# opo_iki.net
KiCad netlist of a schematic drawn in EAGLE
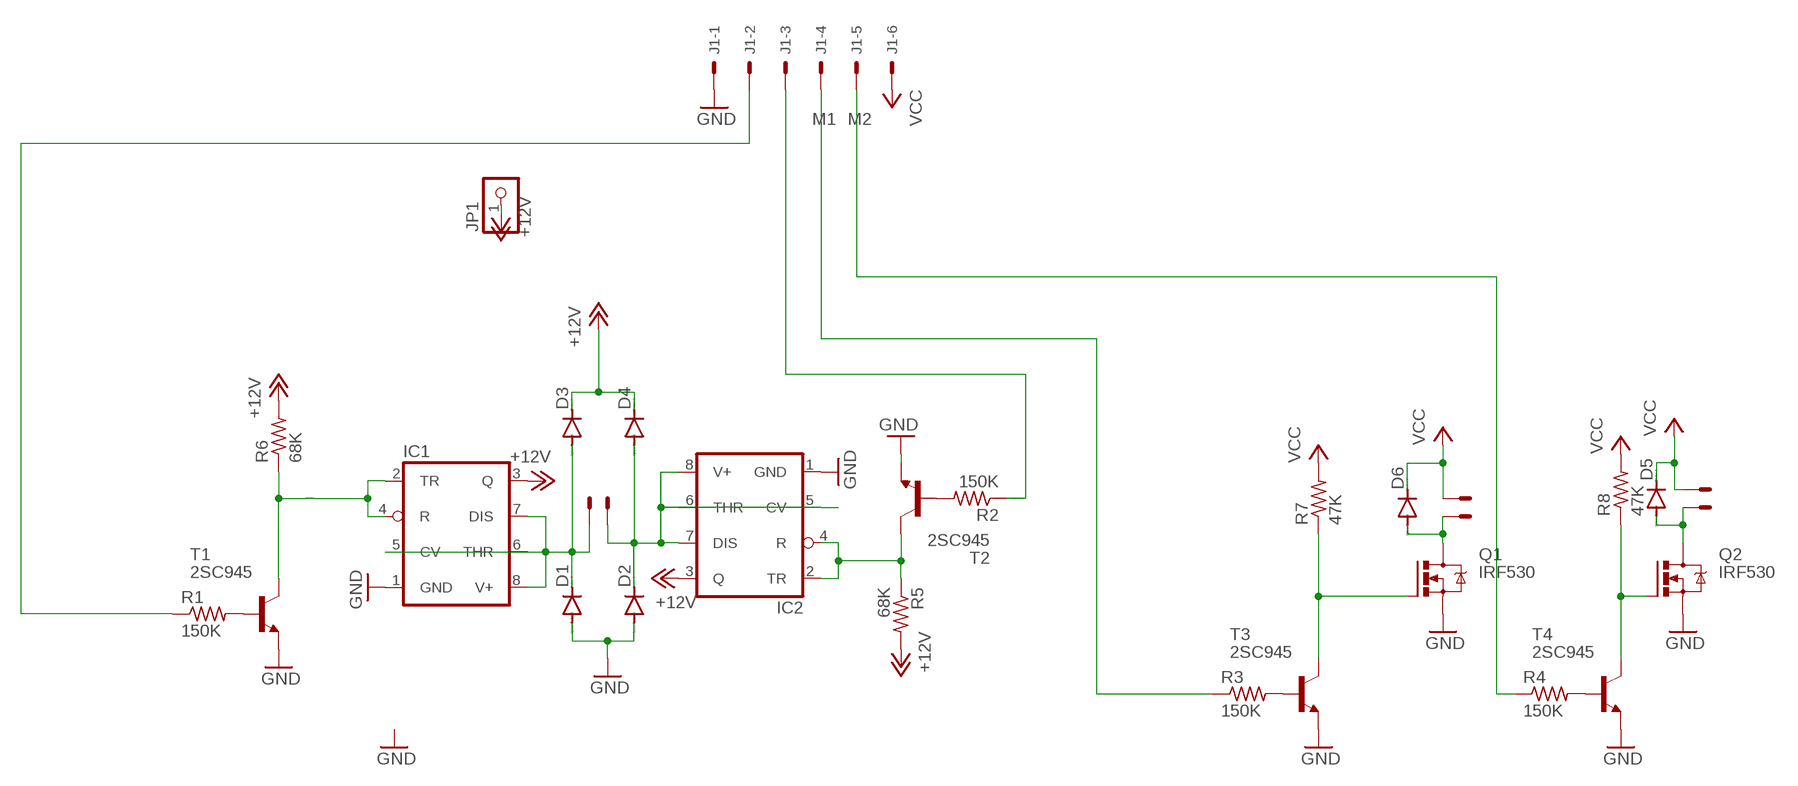
[diagram p0: schematic, sheet 1]

(export (version "E")
  (design (tool "Eeschema 10.0.6"))
  (components
    (comp (ref "D1")
      (value "1N4004")
      (footprint "eagle-import:DO41-10")
      (libsource (lib "eagle-import") (part "1N4004"))
    )
    (comp (ref "D2")
      (value "1N4004")
      (footprint "eagle-import:DO41-10")
      (libsource (lib "eagle-import") (part "1N4004"))
    )
    (comp (ref "D3")
      (value "1N4004")
      (footprint "eagle-import:DO41-10")
      (libsource (lib "eagle-import") (part "1N4004"))
    )
    (comp (ref "D4")
      (value "1N4004")
      (footprint "eagle-import:DO41-10")
      (libsource (lib "eagle-import") (part "1N4004"))
    )
    (comp (ref "D5")
      (value "1N4004")
      (footprint "eagle-import:DO41-10")
      (libsource (lib "eagle-import") (part "1N4004"))
    )
    (comp (ref "D6")
      (value "1N4004")
      (footprint "eagle-import:DO41-10")
      (libsource (lib "eagle-import") (part "1N4004"))
    )
    (comp (ref "IC1")
      (value "LM555D")
      (footprint "eagle-import:SO08")
      (libsource (lib "eagle-import") (part "555DLM"))
    )
    (comp (ref "IC2")
      (value "LM555D")
      (footprint "eagle-import:SO08")
      (libsource (lib "eagle-import") (part "555DLM"))
    )
    (comp (ref "J1")
      (value "22-27-2061-06")
      (footprint "eagle-import:6410-06")
      (fields (field (name "MF") "MOLEX"))
      (libsource (lib "eagle-import") (part "22-?-0627-2061"))
    )
    (comp (ref "JP1")
      (value "PINHD-1X1")
      (footprint "eagle-import:1X01")
      (libsource (lib "eagle-import") (part "PINHD-1X1"))
    )
    (comp (ref "Q1")
      (value "IRF530")
      (footprint "eagle-import:TO220BV")
      (libsource (lib "eagle-import") (part "IRF530"))
    )
    (comp (ref "Q2")
      (value "IRF530")
      (footprint "eagle-import:TO220BV")
      (libsource (lib "eagle-import") (part "IRF530"))
    )
    (comp (ref "R1")
      (value "150K")
      (footprint "eagle-import:0309_10")
      (libsource (lib "eagle-import") (part "R-US_0309/10"))
    )
    (comp (ref "R2")
      (value "150K")
      (footprint "eagle-import:0309_10")
      (libsource (lib "eagle-import") (part "R-US_0309/10"))
    )
    (comp (ref "R3")
      (value "150K")
      (footprint "eagle-import:0309_10")
      (libsource (lib "eagle-import") (part "R-US_0309/10"))
    )
    (comp (ref "R4")
      (value "150K")
      (footprint "eagle-import:0309_10")
      (libsource (lib "eagle-import") (part "R-US_0309/10"))
    )
    (comp (ref "R5")
      (value "68K")
      (footprint "eagle-import:0309_10")
      (libsource (lib "eagle-import") (part "R-US_0309/10"))
    )
    (comp (ref "R6")
      (value "68K")
      (footprint "eagle-import:0309_10")
      (libsource (lib "eagle-import") (part "R-US_0309/10"))
    )
    (comp (ref "R7")
      (value "47K")
      (footprint "eagle-import:0309_10")
      (libsource (lib "eagle-import") (part "R-US_0309/10"))
    )
    (comp (ref "R8")
      (value "47K")
      (footprint "eagle-import:0309_10")
      (libsource (lib "eagle-import") (part "R-US_0309/10"))
    )
    (comp (ref "T1")
      (value "2SC945")
      (footprint "eagle-import:TO92-ECB")
      (libsource (lib "eagle-import") (part "2SC945"))
    )
    (comp (ref "T2")
      (value "2SC945")
      (footprint "eagle-import:TO92-ECB")
      (libsource (lib "eagle-import") (part "2SC945"))
    )
    (comp (ref "T3")
      (value "2SC945")
      (footprint "eagle-import:TO92-ECB")
      (libsource (lib "eagle-import") (part "2SC945"))
    )
    (comp (ref "T4")
      (value "2SC945")
      (footprint "eagle-import:TO92-ECB")
      (libsource (lib "eagle-import") (part "2SC945"))
    )
    (comp (ref "X1")
      (value "22-23-2021")
      (footprint "eagle-import:22-23-2021")
      (fields (field (name "MF") "MOLEX"))
      (libsource (lib "eagle-import") (part "22-23-2021"))
    )
    (comp (ref "X2")
      (value "22-23-2021")
      (footprint "eagle-import:22-23-2021")
      (fields (field (name "MF") "MOLEX"))
      (libsource (lib "eagle-import") (part "22-23-2021"))
    )
    (comp (ref "X3")
      (value "22-23-2021")
      (footprint "eagle-import:22-23-2021")
      (fields (field (name "MF") "MOLEX"))
      (libsource (lib "eagle-import") (part "22-23-2021"))
    )
  )
  (nets
    (net (code "1") (name "+12V") (class "Default")
      (node (ref "D3") (pin "C") (pinfunction "C_C") (pintype "passive"))
      (node (ref "D4") (pin "C") (pinfunction "C_C") (pintype "passive"))
      (node (ref "IC1") (pin "3") (pinfunction "Q_3") (pintype "output"))
      (node (ref "IC2") (pin "3") (pinfunction "Q_3") (pintype "output"))
      (node (ref "JP1") (pin "1") (pinfunction "1_1") (pintype "passive"))
      (node (ref "R5") (pin "2") (pinfunction "2_2") (pintype "passive"))
      (node (ref "R6") (pin "2") (pinfunction "2_2") (pintype "passive"))
    )
    (net (code "2") (name "/M1") (class "Default")
      (node (ref "J1") (pin "4") (pinfunction "S_4") (pintype "passive"))
      (node (ref "R3") (pin "1") (pinfunction "1_1") (pintype "passive"))
    )
    (net (code "3") (name "/M2") (class "Default")
      (node (ref "J1") (pin "5") (pinfunction "S_5") (pintype "passive"))
      (node (ref "R4") (pin "1") (pinfunction "1_1") (pintype "passive"))
    )
    (net (code "4") (name "GND") (class "Default")
      (node (ref "D1") (pin "A") (pinfunction "A_A") (pintype "passive"))
      (node (ref "D2") (pin "A") (pinfunction "A_A") (pintype "passive"))
      (node (ref "IC1") (pin "1") (pinfunction "GND_1") (pintype "power_in"))
      (node (ref "IC2") (pin "1") (pinfunction "GND_1") (pintype "power_in"))
      (node (ref "J1") (pin "1") (pinfunction "S_1") (pintype "passive"))
      (node (ref "Q1") (pin "S") (pinfunction "S_S") (pintype "passive"))
      (node (ref "Q2") (pin "S") (pinfunction "S_S") (pintype "passive"))
      (node (ref "T1") (pin "E") (pinfunction "E_E") (pintype "passive"))
      (node (ref "T2") (pin "E") (pinfunction "E_E") (pintype "passive"))
      (node (ref "T3") (pin "E") (pinfunction "E_E") (pintype "passive"))
      (node (ref "T4") (pin "E") (pinfunction "E_E") (pintype "passive"))
    )
    (net (code "5") (name "Net-(IC1-CV)") (class "Default")
      (node (ref "D1") (pin "C") (pinfunction "C_C") (pintype "passive"))
      (node (ref "D3") (pin "A") (pinfunction "A_A") (pintype "passive"))
      (node (ref "IC1") (pin "5") (pinfunction "CV_5") (pintype "input"))
      (node (ref "IC1") (pin "6") (pinfunction "THR_6") (pintype "input"))
      (node (ref "IC1") (pin "7") (pinfunction "DIS_7") (pintype "input"))
      (node (ref "IC1") (pin "8") (pinfunction "V+_8") (pintype "power_in"))
      (node (ref "X3") (pin "1") (pinfunction "S_1") (pintype "passive"))
    )
    (net (code "6") (name "Net-(IC1-R)") (class "Default")
      (node (ref "IC1") (pin "2") (pinfunction "TR_2") (pintype "input"))
      (node (ref "IC1") (pin "4") (pinfunction "R_4") (pintype "input"))
      (node (ref "R6") (pin "1") (pinfunction "1_1") (pintype "passive"))
      (node (ref "T1") (pin "C") (pinfunction "C_C") (pintype "passive"))
    )
    (net (code "7") (name "Net-(IC2-CV)") (class "Default")
      (node (ref "D2") (pin "C") (pinfunction "C_C") (pintype "passive"))
      (node (ref "D4") (pin "A") (pinfunction "A_A") (pintype "passive"))
      (node (ref "IC2") (pin "5") (pinfunction "CV_5") (pintype "input"))
      (node (ref "IC2") (pin "6") (pinfunction "THR_6") (pintype "input"))
      (node (ref "IC2") (pin "7") (pinfunction "DIS_7") (pintype "input"))
      (node (ref "IC2") (pin "8") (pinfunction "V+_8") (pintype "power_in"))
      (node (ref "X3") (pin "2") (pinfunction "S_2") (pintype "passive"))
    )
    (net (code "8") (name "Net-(IC2-R)") (class "Default")
      (node (ref "IC2") (pin "2") (pinfunction "TR_2") (pintype "input"))
      (node (ref "IC2") (pin "4") (pinfunction "R_4") (pintype "input"))
      (node (ref "R5") (pin "1") (pinfunction "1_1") (pintype "passive"))
      (node (ref "T2") (pin "C") (pinfunction "C_C") (pintype "passive"))
    )
    (net (code "9") (name "Net-(J1B-S)") (class "Default")
      (node (ref "J1") (pin "2") (pinfunction "S_2") (pintype "passive"))
      (node (ref "R1") (pin "1") (pinfunction "1_1") (pintype "passive"))
    )
    (net (code "10") (name "Net-(J1C-S)") (class "Default")
      (node (ref "J1") (pin "3") (pinfunction "S_3") (pintype "passive"))
      (node (ref "R2") (pin "1") (pinfunction "1_1") (pintype "passive"))
    )
    (net (code "11") (name "Net-(Q1-PadG)") (class "Default")
      (node (ref "Q1") (pin "G") (pinfunction "G_G") (pintype "passive"))
      (node (ref "R7") (pin "1") (pinfunction "1_1") (pintype "passive"))
      (node (ref "T3") (pin "C") (pinfunction "C_C") (pintype "passive"))
    )
    (net (code "12") (name "Net-(Q2-PadG)") (class "Default")
      (node (ref "Q2") (pin "G") (pinfunction "G_G") (pintype "passive"))
      (node (ref "R8") (pin "1") (pinfunction "1_1") (pintype "passive"))
      (node (ref "T4") (pin "C") (pinfunction "C_C") (pintype "passive"))
    )
    (net (code "13") (name "Net-(R1-Pad2)") (class "Default")
      (node (ref "R1") (pin "2") (pinfunction "2_2") (pintype "passive"))
      (node (ref "T1") (pin "B") (pinfunction "B_B") (pintype "passive"))
    )
    (net (code "14") (name "Net-(R2-Pad2)") (class "Default")
      (node (ref "R2") (pin "2") (pinfunction "2_2") (pintype "passive"))
      (node (ref "T2") (pin "B") (pinfunction "B_B") (pintype "passive"))
    )
    (net (code "15") (name "Net-(R3-Pad2)") (class "Default")
      (node (ref "R3") (pin "2") (pinfunction "2_2") (pintype "passive"))
      (node (ref "T3") (pin "B") (pinfunction "B_B") (pintype "passive"))
    )
    (net (code "16") (name "Net-(R4-Pad2)") (class "Default")
      (node (ref "R4") (pin "2") (pinfunction "2_2") (pintype "passive"))
      (node (ref "T4") (pin "B") (pinfunction "B_B") (pintype "passive"))
    )
    (net (code "17") (name "Net-(X1B-S)") (class "Default")
      (node (ref "D6") (pin "A") (pinfunction "A_A") (pintype "passive"))
      (node (ref "Q1") (pin "D") (pinfunction "D_D") (pintype "passive"))
      (node (ref "X1") (pin "2") (pinfunction "S_2") (pintype "passive"))
    )
    (net (code "18") (name "Net-(X2B-S)") (class "Default")
      (node (ref "D5") (pin "A") (pinfunction "A_A") (pintype "passive"))
      (node (ref "Q2") (pin "D") (pinfunction "D_D") (pintype "passive"))
      (node (ref "X2") (pin "2") (pinfunction "S_2") (pintype "passive"))
    )
    (net (code "19") (name "VCC") (class "Default")
      (node (ref "D5") (pin "C") (pinfunction "C_C") (pintype "passive"))
      (node (ref "D6") (pin "C") (pinfunction "C_C") (pintype "passive"))
      (node (ref "J1") (pin "6") (pinfunction "S_6") (pintype "passive"))
      (node (ref "R7") (pin "2") (pinfunction "2_2") (pintype "passive"))
      (node (ref "R8") (pin "2") (pinfunction "2_2") (pintype "passive"))
      (node (ref "X1") (pin "1") (pinfunction "S_1") (pintype "passive"))
      (node (ref "X2") (pin "1") (pinfunction "S_1") (pintype "passive"))
    )
  )
)
